# SFP.net
KiCad netlist of a schematic drawn in Altium Designer
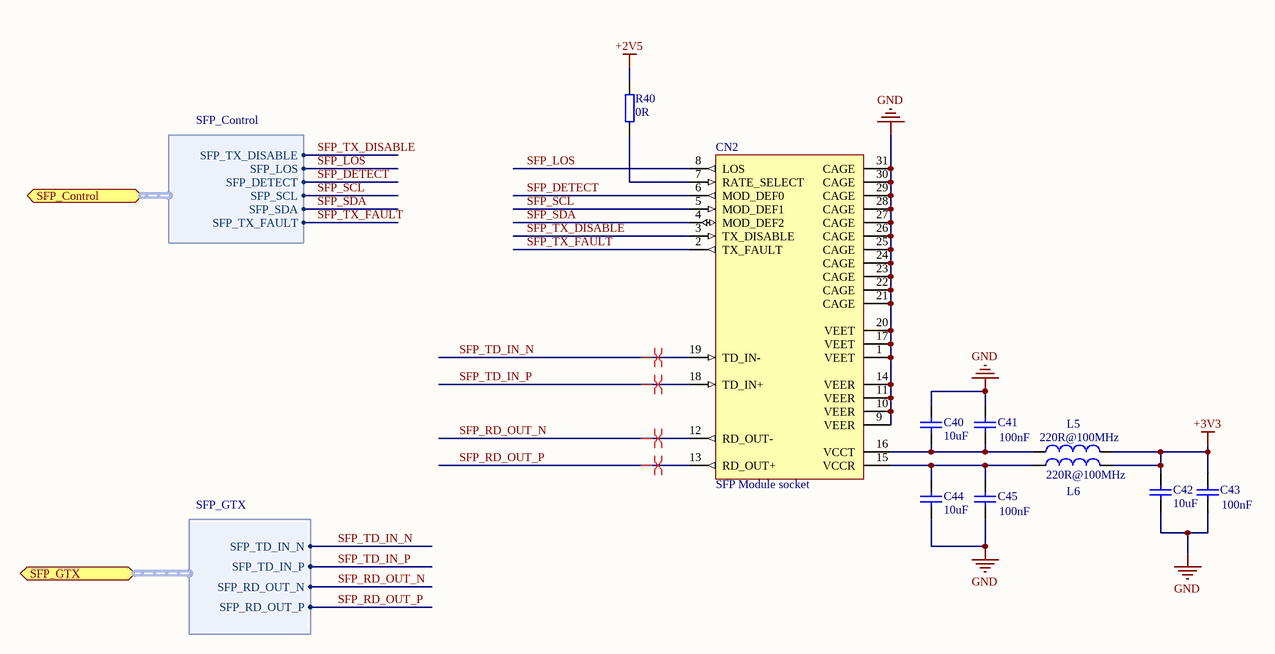
[diagram p0: SFP.SchDoc]

(export (version "E")
  (design (tool "Eeschema 10.0.6"))
  (components
    (comp (ref "C40")
      (value "10uF")
      (footprint "CC1608-0603")
      (description "Capacitor")
      (fields
        (field (name "TOLERANCE") "±20%")
        (field (name "VOLTAGE") "6.3V")
        (field (name "PUBLISHER") "Altium Limited")
      )
      (libsource (lib "wr_switch") (part "Cap"))
    )
    (comp (ref "C41")
      (value "100nF")
      (footprint "CC1005-0402")
      (description "Capacitor")
      (fields
        (field (name "TOLERANCE") "±10%")
        (field (name "VOLTAGE") "16V")
        (field (name "PUBLISHER") "Altium Limited")
      )
      (libsource (lib "wr_switch") (part "Cap"))
    )
    (comp (ref "C42")
      (value "10uF")
      (footprint "CC1608-0603")
      (description "Capacitor")
      (fields
        (field (name "TOLERANCE") "±20%")
        (field (name "VOLTAGE") "6.3V")
        (field (name "PUBLISHER") "Altium Limited")
      )
      (libsource (lib "wr_switch") (part "Cap"))
    )
    (comp (ref "C43")
      (value "100nF")
      (footprint "CC1005-0402")
      (description "Capacitor")
      (fields
        (field (name "TOLERANCE") "±10%")
        (field (name "VOLTAGE") "16V")
        (field (name "PUBLISHER") "Altium Limited")
      )
      (libsource (lib "wr_switch") (part "Cap"))
    )
    (comp (ref "C44")
      (value "10uF")
      (footprint "CC1608-0603")
      (description "Capacitor")
      (fields
        (field (name "TOLERANCE") "±20%")
        (field (name "VOLTAGE") "6.3V")
        (field (name "PUBLISHER") "Altium Limited")
      )
      (libsource (lib "wr_switch") (part "Cap"))
    )
    (comp (ref "C45")
      (value "100nF")
      (footprint "CC1005-0402")
      (description "Capacitor")
      (fields
        (field (name "TOLERANCE") "±10%")
        (field (name "VOLTAGE") "16V")
        (field (name "PUBLISHER") "Altium Limited")
      )
      (libsource (lib "wr_switch") (part "Cap"))
    )
    (comp (ref "CN2")
      (value "SFP Module socket")
      (footprint "SFP_SINGLE_PORT")
      (description "Socket for SFP module")
      (libsource (lib "wr_switch") (part "SFP_SOCKET_SINGLE"))
    )
    (comp (ref "L5")
      (value "220R@100MHz Ferrite Bead")
      (footprint "0603")
      (description "ferrite bead")
      (fields (field (name "IMPEDANCE") "220R@100MHz"))
      (libsource (lib "wr_switch") (part "L_FERRITE_BEAD"))
    )
    (comp (ref "L6")
      (value "220R@100MHz Ferrite Bead")
      (footprint "0603")
      (description "ferrite bead")
      (fields (field (name "IMPEDANCE") "220R@100MHz"))
      (libsource (lib "wr_switch") (part "L_FERRITE_BEAD"))
    )
    (comp (ref "R40")
      (value "0R")
      (footprint "0603")
      (description "SMD Resistor")
      (libsource (lib "wr_switch") (part "RES_SMD"))
    )
  )
  (nets
    (net (code "3") (name "+2V5") (class "Default")
      (node (ref "R40") (pin "1") (pinfunction "1_1") (pintype "passive"))
    )
    (net (code "4") (name "+3V3") (class "Default")
      (node (ref "C42") (pin "1") (pinfunction "1_1") (pintype "passive"))
      (node (ref "C43") (pin "2") (pinfunction "2_2") (pintype "passive"))
      (node (ref "L5") (pin "2") (pinfunction "2_2") (pintype "passive"))
      (node (ref "L6") (pin "2") (pinfunction "2_2") (pintype "passive"))
    )
    (net (code "5") (name "/SFP_DETECT") (class "Default")
      (node (ref "CN2") (pin "6") (pinfunction "MOD_DEF0_6") (pintype "output"))
    )
    (net (code "6") (name "/SFP_LOS") (class "Default")
      (node (ref "CN2") (pin "8") (pinfunction "LOS_8") (pintype "output"))
    )
    (net (code "7") (name "/SFP_RD_OUT_N") (class "Default")
      (node (ref "CN2") (pin "12") (pinfunction "RD_OUT-_12") (pintype "output"))
    )
    (net (code "8") (name "/SFP_RD_OUT_P") (class "Default")
      (node (ref "CN2") (pin "13") (pinfunction "RD_OUT+_13") (pintype "output"))
    )
    (net (code "9") (name "/SFP_SCL") (class "Default")
      (node (ref "CN2") (pin "5") (pinfunction "MOD_DEF1_5") (pintype "input"))
    )
    (net (code "10") (name "/SFP_SDA") (class "Default")
      (node (ref "CN2") (pin "4") (pinfunction "MOD_DEF2_4") (pintype "bidirectional"))
    )
    (net (code "11") (name "/SFP_TD_IN_N") (class "Default")
      (node (ref "CN2") (pin "19") (pinfunction "TD_IN-_19") (pintype "input"))
    )
    (net (code "12") (name "/SFP_TD_IN_P") (class "Default")
      (node (ref "CN2") (pin "18") (pinfunction "TD_IN+_18") (pintype "input"))
    )
    (net (code "13") (name "/SFP_TX_DISABLE") (class "Default")
      (node (ref "CN2") (pin "3") (pinfunction "TX_DISABLE_3") (pintype "input"))
    )
    (net (code "14") (name "/SFP_TX_FAULT") (class "Default")
      (node (ref "CN2") (pin "2") (pinfunction "TX_FAULT_2") (pintype "output"))
    )
    (net (code "17") (name "GND") (class "Default")
      (node (ref "C40") (pin "1") (pinfunction "1_1") (pintype "passive"))
      (node (ref "C41") (pin "2") (pinfunction "2_2") (pintype "passive"))
      (node (ref "C42") (pin "2") (pinfunction "2_2") (pintype "passive"))
      (node (ref "C43") (pin "1") (pinfunction "1_1") (pintype "passive"))
      (node (ref "C44") (pin "2") (pinfunction "2_2") (pintype "passive"))
      (node (ref "C45") (pin "1") (pinfunction "1_1") (pintype "passive"))
      (node (ref "CN2") (pin "1") (pinfunction "VEET_1") (pintype "power_in"))
      (node (ref "CN2") (pin "10") (pinfunction "VEER_10") (pintype "power_in"))
      (node (ref "CN2") (pin "11") (pinfunction "VEER_11") (pintype "power_in"))
      (node (ref "CN2") (pin "14") (pinfunction "VEER_14") (pintype "power_in"))
      (node (ref "CN2") (pin "17") (pinfunction "VEET_17") (pintype "power_in"))
      (node (ref "CN2") (pin "20") (pinfunction "VEET_20") (pintype "power_in"))
      (node (ref "CN2") (pin "21") (pinfunction "CAGE_21") (pintype "power_in"))
      (node (ref "CN2") (pin "22") (pinfunction "CAGE_22") (pintype "power_in"))
      (node (ref "CN2") (pin "23") (pinfunction "CAGE_23") (pintype "power_in"))
      (node (ref "CN2") (pin "24") (pinfunction "CAGE_24") (pintype "power_in"))
      (node (ref "CN2") (pin "25") (pinfunction "CAGE_25") (pintype "power_in"))
      (node (ref "CN2") (pin "26") (pinfunction "CAGE_26") (pintype "power_in"))
      (node (ref "CN2") (pin "27") (pinfunction "CAGE_27") (pintype "power_in"))
      (node (ref "CN2") (pin "28") (pinfunction "CAGE_28") (pintype "power_in"))
      (node (ref "CN2") (pin "29") (pinfunction "CAGE_29") (pintype "power_in"))
      (node (ref "CN2") (pin "30") (pinfunction "CAGE_30") (pintype "power_in"))
      (node (ref "CN2") (pin "31") (pinfunction "CAGE_31") (pintype "power_in"))
      (node (ref "CN2") (pin "9") (pinfunction "VEER_9") (pintype "power_in"))
    )
    (net (code "18") (name "Net-(CN2-RATE_SELECT)") (class "Default")
      (node (ref "CN2") (pin "7") (pinfunction "RATE_SELECT_7") (pintype "input"))
      (node (ref "R40") (pin "2") (pinfunction "2_2") (pintype "passive"))
    )
    (net (code "19") (name "Net-(CN2-VCCR)") (class "Default")
      (node (ref "C44") (pin "1") (pinfunction "1_1") (pintype "passive"))
      (node (ref "C45") (pin "2") (pinfunction "2_2") (pintype "passive"))
      (node (ref "CN2") (pin "15") (pinfunction "VCCR_15") (pintype "power_in"))
      (node (ref "L6") (pin "1") (pinfunction "1_1") (pintype "passive"))
    )
    (net (code "20") (name "Net-(CN2-VCCT)") (class "Default")
      (node (ref "C40") (pin "2") (pinfunction "2_2") (pintype "passive"))
      (node (ref "C41") (pin "1") (pinfunction "1_1") (pintype "passive"))
      (node (ref "CN2") (pin "16") (pinfunction "VCCT_16") (pintype "power_in"))
      (node (ref "L5") (pin "1") (pinfunction "1_1") (pintype "passive"))
    )
  )
)
